# tfa_sensor_v12.net
KiCad netlist of a schematic drawn in EAGLE
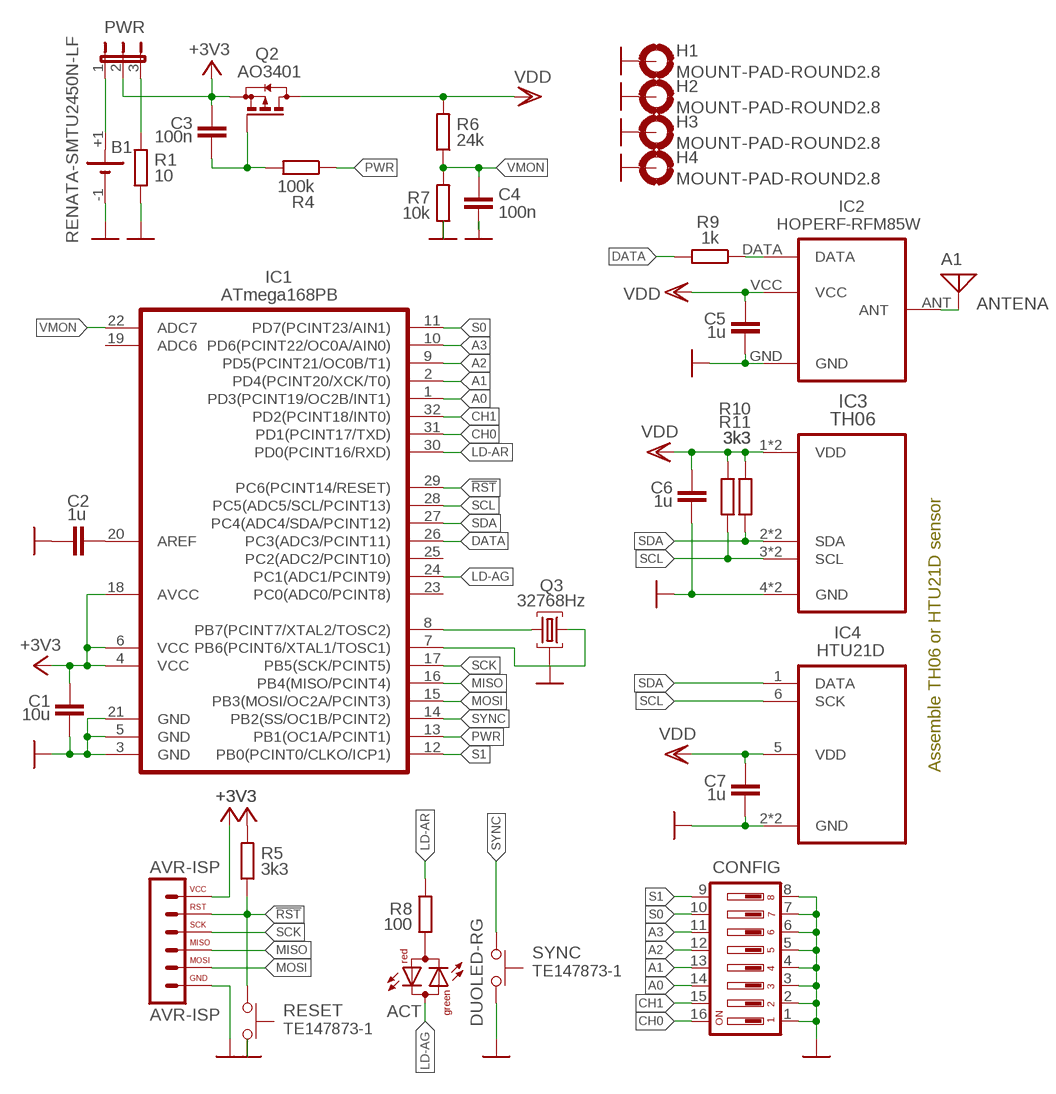
[diagram p0: schematic, sheet 1]

(export (version "E")
  (design (tool "Eeschema 10.0.6"))
  (components
    (comp (ref "A1")
      (value "ANTENA")
      (footprint "eagle-import:ANT-433MHZ-SPIRAL")
      (libsource (lib "eagle-import") (part "ANTENA"))
    )
    (comp (ref "ACT")
      (value "DUOLED-RG")
      (footprint "eagle-import:LED3MM")
      (libsource (lib "eagle-import") (part "DUOLED-RG"))
    )
    (comp (ref "AVR-ISP")
      (value "AVR-ISP")
      (footprint "eagle-import:SIL6-RNDPRESS")
      (libsource (lib "eagle-import") (part "AVR_SPINRP"))
    )
    (comp (ref "B1")
      (value "RENATA-SMTU2450N-LF")
      (footprint "eagle-import:RENATA-SMTU2450N-LF")
      (libsource (lib "eagle-import") (part "RENATA-HU1632-LF2450"))
    )
    (comp (ref "C1")
      (value "10u")
      (footprint "eagle-import:C0805K")
      (libsource (lib "eagle-import") (part "C-EUC0805K"))
    )
    (comp (ref "C2")
      (value "1u")
      (footprint "eagle-import:C0805K")
      (libsource (lib "eagle-import") (part "C-EUC0805K"))
    )
    (comp (ref "C3")
      (value "100n")
      (footprint "eagle-import:C0603K")
      (libsource (lib "eagle-import") (part "C-EUC0603K"))
    )
    (comp (ref "C4")
      (value "100n")
      (footprint "eagle-import:C0603K")
      (libsource (lib "eagle-import") (part "C-EUC0603K"))
    )
    (comp (ref "C5")
      (value "1u")
      (footprint "eagle-import:C0805K")
      (libsource (lib "eagle-import") (part "C-EUC0805K"))
    )
    (comp (ref "C6")
      (value "1u")
      (footprint "eagle-import:C0805K")
      (libsource (lib "eagle-import") (part "C-EUC0805K"))
    )
    (comp (ref "C7")
      (value "1u")
      (footprint "eagle-import:C0603K")
      (libsource (lib "eagle-import") (part "C-EUC0603K"))
    )
    (comp (ref "CONFIG")
      (value "DIP08YL")
      (footprint "eagle-import:DIP08YL")
      (libsource (lib "eagle-import") (part "DIP08YL"))
    )
    (comp (ref "H1")
      (value "MOUNT-PAD-ROUND2.8")
      (footprint "eagle-import:2,8-PAD")
      (libsource (lib "eagle-import") (part "MOUNT-PAD-ROUND2.8"))
    )
    (comp (ref "H2")
      (value "MOUNT-PAD-ROUND2.8")
      (footprint "eagle-import:2,8-PAD")
      (libsource (lib "eagle-import") (part "MOUNT-PAD-ROUND2.8"))
    )
    (comp (ref "H3")
      (value "MOUNT-PAD-ROUND2.8")
      (footprint "eagle-import:2,8-PAD")
      (libsource (lib "eagle-import") (part "MOUNT-PAD-ROUND2.8"))
    )
    (comp (ref "H4")
      (value "MOUNT-PAD-ROUND2.8")
      (footprint "eagle-import:2,8-PAD")
      (libsource (lib "eagle-import") (part "MOUNT-PAD-ROUND2.8"))
    )
    (comp (ref "IC1")
      (value "ATmega168PB")
      (footprint "eagle-import:TQFP32")
      (libsource (lib "eagle-import") (part "ATMEGA88T"))
    )
    (comp (ref "IC2")
      (value "HOPERF-RFM85W")
      (footprint "eagle-import:HOPERF-RFM85W")
      (libsource (lib "eagle-import") (part "HOPERF-RFM85W"))
    )
    (comp (ref "IC3")
      (value "TH06")
      (footprint "eagle-import:TH06")
      (libsource (lib "eagle-import") (part "TH06"))
    )
    (comp (ref "IC4")
      (value "HTU21D")
      (footprint "eagle-import:DFN6-RH")
      (libsource (lib "eagle-import") (part "HTU21D"))
    )
    (comp (ref "PWR")
      (value "JP2EB")
      (footprint "eagle-import:JP2YB")
      (libsource (lib "eagle-import") (part "JP2EB"))
    )
    (comp (ref "Q2")
      (value "AO3401")
      (footprint "eagle-import:SOT23")
      (libsource (lib "eagle-import") (part "BSS84"))
    )
    (comp (ref "Q3")
      (value "32768Hz")
      (footprint "eagle-import:CMJ206T")
      (libsource (lib "eagle-import") (part "CMJ206T"))
    )
    (comp (ref "R1")
      (value "10")
      (footprint "eagle-import:R0805")
      (libsource (lib "eagle-import") (part "R-EU_R0805"))
    )
    (comp (ref "R4")
      (value "100k")
      (footprint "eagle-import:R0603")
      (libsource (lib "eagle-import") (part "R-EU_R0603"))
    )
    (comp (ref "R5")
      (value "3k3")
      (footprint "eagle-import:R0603")
      (libsource (lib "eagle-import") (part "R-EU_R0603"))
    )
    (comp (ref "R6")
      (value "24k")
      (footprint "eagle-import:R0603")
      (libsource (lib "eagle-import") (part "R-EU_R0603"))
    )
    (comp (ref "R7")
      (value "10k")
      (footprint "eagle-import:R0603")
      (libsource (lib "eagle-import") (part "R-EU_R0603"))
    )
    (comp (ref "R8")
      (value "100")
      (footprint "eagle-import:R0603")
      (libsource (lib "eagle-import") (part "R-EU_R0603"))
    )
    (comp (ref "R9")
      (value "1k")
      (footprint "eagle-import:R0603")
      (libsource (lib "eagle-import") (part "R-EU_R0603"))
    )
    (comp (ref "R10")
      (value "3k3")
      (footprint "eagle-import:R0603")
      (libsource (lib "eagle-import") (part "R-EU_R0603"))
    )
    (comp (ref "R11")
      (value "3k3")
      (footprint "eagle-import:R0603")
      (libsource (lib "eagle-import") (part "R-EU_R0603"))
    )
    (comp (ref "RESET")
      (value "TE147873-1")
      (footprint "eagle-import:TE-147873-1")
      (libsource (lib "eagle-import") (part "CUDL1TE147873-1"))
    )
    (comp (ref "SYNC")
      (value "TE147873-1")
      (footprint "eagle-import:CUDL1")
      (libsource (lib "eagle-import") (part "CUDL1_A"))
    )
  )
  (nets
    (net (code "1") (name "+3V3") (class "Default")
      (node (ref "AVR-ISP") (pin "6") (pinfunction "6_6") (pintype "passive"))
      (node (ref "C1") (pin "1") (pinfunction "1_1") (pintype "passive"))
      (node (ref "C3") (pin "1") (pinfunction "1_1") (pintype "passive"))
      (node (ref "IC1") (pin "18") (pinfunction "AVCC_18") (pintype "power_in"))
      (node (ref "IC1") (pin "4") (pinfunction "VCC_4") (pintype "power_in"))
      (node (ref "IC1") (pin "6") (pinfunction "VCC_6") (pintype "power_in"))
      (node (ref "PWR") (pin "2") (pinfunction "2_2") (pintype "passive"))
      (node (ref "Q2") (pin "2") (pinfunction "S_2") (pintype "passive"))
      (node (ref "R5") (pin "2") (pinfunction "2_2") (pintype "passive"))
    )
    (net (code "2") (name "/~{RST}") (class "Default")
      (node (ref "AVR-ISP") (pin "5") (pinfunction "5_5") (pintype "passive"))
      (node (ref "IC1") (pin "29") (pinfunction "PC6(PCINT14/RESET)_29") (pintype "bidirectional"))
      (node (ref "R5") (pin "1") (pinfunction "1_1") (pintype "passive"))
      (node (ref "RESET") (pin "P$2") (pinfunction "P$2_P$2") (pintype "passive"))
    )
    (net (code "3") (name "A0") (class "Default")
      (node (ref "CONFIG") (pin "14") (pinfunction "14_14") (pintype "passive"))
      (node (ref "IC1") (pin "1") (pinfunction "PD3(PCINT19/OC2B/INT1)_1") (pintype "bidirectional"))
    )
    (net (code "4") (name "A1") (class "Default")
      (node (ref "CONFIG") (pin "13") (pinfunction "13_13") (pintype "passive"))
      (node (ref "IC1") (pin "2") (pinfunction "PD4(PCINT20/XCK/T0)_2") (pintype "bidirectional"))
    )
    (net (code "5") (name "A2") (class "Default")
      (node (ref "CONFIG") (pin "12") (pinfunction "12_12") (pintype "passive"))
      (node (ref "IC1") (pin "9") (pinfunction "PD5(PCINT21/OC0B/T1)_9") (pintype "bidirectional"))
    )
    (net (code "6") (name "A3") (class "Default")
      (node (ref "CONFIG") (pin "11") (pinfunction "11_11") (pintype "passive"))
      (node (ref "IC1") (pin "10") (pinfunction "PD6(PCINT22/OC0A/AIN0)_10") (pintype "bidirectional"))
    )
    (net (code "7") (name "CH0") (class "Default")
      (node (ref "CONFIG") (pin "16") (pinfunction "16_16") (pintype "passive"))
      (node (ref "IC1") (pin "31") (pinfunction "PD1(PCINT17/TXD)_31") (pintype "bidirectional"))
    )
    (net (code "8") (name "CH1") (class "Default")
      (node (ref "CONFIG") (pin "15") (pinfunction "15_15") (pintype "passive"))
      (node (ref "IC1") (pin "32") (pinfunction "PD2(PCINT18/INT0)_32") (pintype "bidirectional"))
    )
    (net (code "9") (name "DATA") (class "Default")
      (node (ref "IC1") (pin "26") (pinfunction "PC3(ADC3/PCINT11)_26") (pintype "bidirectional"))
      (node (ref "R9") (pin "2") (pinfunction "2_2") (pintype "passive"))
    )
    (net (code "10") (name "GND") (class "Default")
      (node (ref "AVR-ISP") (pin "1") (pinfunction "1_1") (pintype "passive"))
      (node (ref "B1") (pin "-1") (pinfunction "-_-1") (pintype "passive"))
      (node (ref "C1") (pin "2") (pinfunction "2_2") (pintype "passive"))
      (node (ref "C2") (pin "1") (pinfunction "1_1") (pintype "passive"))
      (node (ref "C4") (pin "2") (pinfunction "2_2") (pintype "passive"))
      (node (ref "C5") (pin "2") (pinfunction "2_2") (pintype "passive"))
      (node (ref "C6") (pin "2") (pinfunction "2_2") (pintype "passive"))
      (node (ref "C7") (pin "2") (pinfunction "2_2") (pintype "passive"))
      (node (ref "CONFIG") (pin "1") (pinfunction "1_1") (pintype "passive"))
      (node (ref "CONFIG") (pin "2") (pinfunction "2_2") (pintype "passive"))
      (node (ref "CONFIG") (pin "3") (pinfunction "3_3") (pintype "passive"))
      (node (ref "CONFIG") (pin "4") (pinfunction "4_4") (pintype "passive"))
      (node (ref "CONFIG") (pin "5") (pinfunction "5_5") (pintype "passive"))
      (node (ref "CONFIG") (pin "6") (pinfunction "6_6") (pintype "passive"))
      (node (ref "CONFIG") (pin "7") (pinfunction "7_7") (pintype "passive"))
      (node (ref "CONFIG") (pin "8") (pinfunction "8_8") (pintype "passive"))
      (node (ref "H1") (pin "B2,8") (pinfunction "MOUNT_B2,8") (pintype "passive"))
      (node (ref "H2") (pin "B2,8") (pinfunction "MOUNT_B2,8") (pintype "passive"))
      (node (ref "H3") (pin "B2,8") (pinfunction "MOUNT_B2,8") (pintype "passive"))
      (node (ref "H4") (pin "B2,8") (pinfunction "MOUNT_B2,8") (pintype "passive"))
      (node (ref "IC1") (pin "21") (pinfunction "GND_21") (pintype "power_in"))
      (node (ref "IC1") (pin "3") (pinfunction "GND_3") (pintype "power_in"))
      (node (ref "IC1") (pin "5") (pinfunction "GND_5") (pintype "power_in"))
      (node (ref "IC2") (pin "GND") (pinfunction "GND_GND") (pintype "bidirectional"))
      (node (ref "IC3") (pin "14") (pinfunction "GND_14") (pintype "passive"))
      (node (ref "IC3") (pin "4") (pinfunction "GND_4") (pintype "passive"))
      (node (ref "IC4") (pin "2") (pinfunction "GND_2") (pintype "bidirectional"))
      (node (ref "IC4") (pin "EP") (pinfunction "GND_EP") (pintype "bidirectional"))
      (node (ref "Q3") (pin "S") (pinfunction "3_S") (pintype "passive"))
      (node (ref "R1") (pin "2") (pinfunction "2_2") (pintype "passive"))
      (node (ref "R7") (pin "1") (pinfunction "1_1") (pintype "passive"))
      (node (ref "RESET") (pin "P$1") (pinfunction "P$1_P$1") (pintype "passive"))
      (node (ref "SYNC") (pin "1") (pinfunction "P$1_1") (pintype "passive"))
      (node (ref "SYNC") (pin "2") (pinfunction "P$1_2") (pintype "passive"))
    )
    (net (code "11") (name "LD-AG") (class "Default")
      (node (ref "ACT") (pin "K") (pinfunction "C_K") (pintype "passive"))
      (node (ref "IC1") (pin "24") (pinfunction "PC1(ADC1/PCINT9)_24") (pintype "bidirectional"))
    )
    (net (code "12") (name "LD-AR") (class "Default")
      (node (ref "IC1") (pin "30") (pinfunction "PD0(PCINT16/RXD)_30") (pintype "bidirectional"))
      (node (ref "R8") (pin "2") (pinfunction "2_2") (pintype "passive"))
    )
    (net (code "13") (name "MISO") (class "Default")
      (node (ref "AVR-ISP") (pin "3") (pinfunction "3_3") (pintype "passive"))
      (node (ref "IC1") (pin "16") (pinfunction "PB4(MISO/PCINT4)_16") (pintype "bidirectional"))
    )
    (net (code "14") (name "MOSI") (class "Default")
      (node (ref "AVR-ISP") (pin "2") (pinfunction "2_2") (pintype "passive"))
      (node (ref "IC1") (pin "15") (pinfunction "PB3(MOSI/OC2A/PCINT3)_15") (pintype "bidirectional"))
    )
    (net (code "15") (name "Net-(A1-1)") (class "Default")
      (node (ref "A1") (pin "P$1") (pinfunction "1_P$1") (pintype "output"))
      (node (ref "IC2") (pin "ANT") (pinfunction "ANT_ANT") (pintype "bidirectional"))
    )
    (net (code "16") (name "Net-(ACT-PadA)") (class "Default")
      (node (ref "ACT") (pin "A") (pinfunction "A_A") (pintype "passive"))
      (node (ref "R8") (pin "1") (pinfunction "1_1") (pintype "passive"))
    )
    (net (code "17") (name "Net-(B1-+)") (class "Default")
      (node (ref "B1") (pin "+1") (pinfunction "+_+1") (pintype "passive"))
      (node (ref "PWR") (pin "1") (pinfunction "1_1") (pintype "passive"))
    )
    (net (code "18") (name "Net-(IC1-AREF)") (class "Default")
      (node (ref "C2") (pin "2") (pinfunction "2_2") (pintype "passive"))
      (node (ref "IC1") (pin "20") (pinfunction "AREF_20") (pintype "input"))
    )
    (net (code "19") (name "Net-(IC1-PB6(PCINT6{slash}XTAL1{slash}TOSC1))") (class "Default")
      (node (ref "IC1") (pin "7") (pinfunction "PB6(PCINT6/XTAL1/TOSC1)_7") (pintype "bidirectional"))
      (node (ref "Q3") (pin "X1") (pinfunction "1_X1") (pintype "passive"))
    )
    (net (code "20") (name "Net-(IC1-PB7(PCINT7{slash}XTAL2{slash}TOSC2))") (class "Default")
      (node (ref "IC1") (pin "8") (pinfunction "PB7(PCINT7/XTAL2/TOSC2)_8") (pintype "bidirectional"))
      (node (ref "Q3") (pin "X2") (pinfunction "2_X2") (pintype "passive"))
    )
    (net (code "21") (name "Net-(IC2-PadDATA)") (class "Default")
      (node (ref "IC2") (pin "DATA") (pinfunction "DATA_DATA") (pintype "bidirectional"))
      (node (ref "R9") (pin "1") (pinfunction "1_1") (pintype "passive"))
    )
    (net (code "22") (name "Net-(PWR-Pad3)") (class "Default")
      (node (ref "PWR") (pin "3") (pinfunction "3_3") (pintype "passive"))
      (node (ref "R1") (pin "1") (pinfunction "1_1") (pintype "passive"))
    )
    (net (code "23") (name "Net-(Q2-G)") (class "Default")
      (node (ref "C3") (pin "2") (pinfunction "2_2") (pintype "passive"))
      (node (ref "Q2") (pin "1") (pinfunction "G_1") (pintype "passive"))
      (node (ref "R4") (pin "2") (pinfunction "2_2") (pintype "passive"))
    )
    (net (code "24") (name "PWR") (class "Default")
      (node (ref "IC1") (pin "13") (pinfunction "PB1(OC1A/PCINT1)_13") (pintype "bidirectional"))
      (node (ref "R4") (pin "1") (pinfunction "1_1") (pintype "passive"))
    )
    (net (code "25") (name "S0") (class "Default")
      (node (ref "CONFIG") (pin "10") (pinfunction "10_10") (pintype "passive"))
      (node (ref "IC1") (pin "11") (pinfunction "PD7(PCINT23/AIN1)_11") (pintype "bidirectional"))
    )
    (net (code "26") (name "S1") (class "Default")
      (node (ref "CONFIG") (pin "9") (pinfunction "9_9") (pintype "passive"))
      (node (ref "IC1") (pin "12") (pinfunction "PB0(PCINT0/CLKO/ICP1)_12") (pintype "bidirectional"))
    )
    (net (code "27") (name "SCK") (class "Default")
      (node (ref "AVR-ISP") (pin "4") (pinfunction "4_4") (pintype "passive"))
      (node (ref "IC1") (pin "17") (pinfunction "PB5(SCK/PCINT5)_17") (pintype "bidirectional"))
    )
    (net (code "28") (name "SCL") (class "Default")
      (node (ref "IC1") (pin "28") (pinfunction "PC5(ADC5/SCL/PCINT13)_28") (pintype "bidirectional"))
      (node (ref "IC3") (pin "13") (pinfunction "SCL_13") (pintype "bidirectional"))
      (node (ref "IC3") (pin "3") (pinfunction "SCL_3") (pintype "bidirectional"))
      (node (ref "IC4") (pin "6") (pinfunction "SCK_6") (pintype "bidirectional"))
      (node (ref "R10") (pin "2") (pinfunction "2_2") (pintype "passive"))
    )
    (net (code "29") (name "SDA") (class "Default")
      (node (ref "IC1") (pin "27") (pinfunction "PC4(ADC4/SDA/PCINT12)_27") (pintype "bidirectional"))
      (node (ref "IC3") (pin "12") (pinfunction "SDA_12") (pintype "bidirectional"))
      (node (ref "IC3") (pin "2") (pinfunction "SDA_2") (pintype "bidirectional"))
      (node (ref "IC4") (pin "1") (pinfunction "DATA_1") (pintype "bidirectional"))
      (node (ref "R11") (pin "2") (pinfunction "2_2") (pintype "passive"))
    )
    (net (code "30") (name "SYNC") (class "Default")
      (node (ref "IC1") (pin "14") (pinfunction "PB2(SS/OC1B/PCINT2)_14") (pintype "bidirectional"))
      (node (ref "SYNC") (pin "3") (pinfunction "P$2_3") (pintype "passive"))
      (node (ref "SYNC") (pin "4") (pinfunction "P$2_4") (pintype "passive"))
    )
    (net (code "31") (name "VDD") (class "Default")
      (node (ref "C5") (pin "1") (pinfunction "1_1") (pintype "passive"))
      (node (ref "C6") (pin "1") (pinfunction "1_1") (pintype "passive"))
      (node (ref "C7") (pin "1") (pinfunction "1_1") (pintype "passive"))
      (node (ref "IC2") (pin "VCC") (pinfunction "VCC_VCC") (pintype "bidirectional"))
      (node (ref "IC3") (pin "1") (pinfunction "VDD_1") (pintype "passive"))
      (node (ref "IC3") (pin "11") (pinfunction "VDD_11") (pintype "passive"))
      (node (ref "IC4") (pin "5") (pinfunction "VDD_5") (pintype "bidirectional"))
      (node (ref "Q2") (pin "3") (pinfunction "D_3") (pintype "passive"))
      (node (ref "R10") (pin "1") (pinfunction "1_1") (pintype "passive"))
      (node (ref "R11") (pin "1") (pinfunction "1_1") (pintype "passive"))
      (node (ref "R6") (pin "2") (pinfunction "2_2") (pintype "passive"))
    )
    (net (code "32") (name "VMON") (class "Default")
      (node (ref "C4") (pin "1") (pinfunction "1_1") (pintype "passive"))
      (node (ref "IC1") (pin "22") (pinfunction "ADC7_22") (pintype "bidirectional"))
      (node (ref "R6") (pin "1") (pinfunction "1_1") (pintype "passive"))
      (node (ref "R7") (pin "2") (pinfunction "2_2") (pintype "passive"))
    )
    (net (code "33") (name "unconnected-(IC1-ADC6-Pad19)") (class "Default")
      (node (ref "IC1") (pin "19") (pinfunction "ADC6_19") (pintype "bidirectional"))
    )
    (net (code "34") (name "unconnected-(IC1-PC0(ADC0{slash}PCINT8)-Pad23)") (class "Default")
      (node (ref "IC1") (pin "23") (pinfunction "PC0(ADC0/PCINT8)_23") (pintype "bidirectional"))
    )
    (net (code "35") (name "unconnected-(IC1-PC2(ADC2{slash}PCINT10)-Pad25)") (class "Default")
      (node (ref "IC1") (pin "25") (pinfunction "PC2(ADC2/PCINT10)_25") (pintype "bidirectional"))
    )
  )
)
